# PWR.net
KiCad netlist of a schematic drawn in Altium Designer
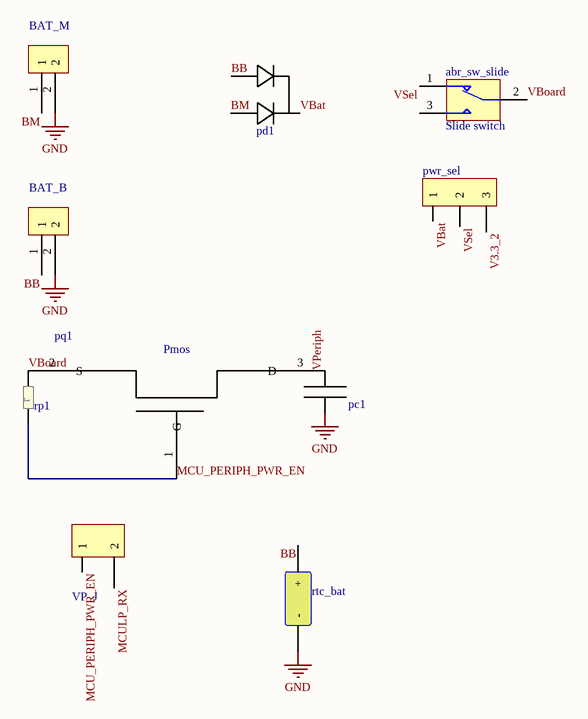
[diagram p0: PWR.SchDoc]

(export (version "E")
  (design (tool "Eeschema 10.0.6"))
  (components
    (comp (ref "abr_sw_slide")
      (value "Slide switch")
      (footprint "abr_sw_slide__r_3d")
      (libsource (lib "lpwireless") (part "Slide switch"))
    )
    (comp (ref "BAT_B")
      (value "YB2 SMD")
      (footprint "abr_sw_yb_2p_3d")
      (libsource (lib "lpwireless") (part "YB2 SMD"))
    )
    (comp (ref "BAT_M")
      (value "YB2 SMD")
      (footprint "abr_sw_yb_2p_3d")
      (libsource (lib "lpwireless") (part "YB2 SMD"))
    )
    (comp (ref "pc1")
      (value "100nf")
      (footprint "abr_cap_0805_3d")
      (libsource (lib "abr_smd_0805_all") (part "abr_cap_0805"))
    )
    (comp (ref "pd1")
      (value "abr_diode_shotkey")
      (footprint "abr_diode_bat54c_3d")
      (libsource (lib "abr_diode_smd") (part "abr_diode_shatkey_bat54c"))
    )
    (comp (ref "pq1")
      (value "irlm6402")
      (footprint "irlm6402")
      (libsource (lib "abr_transistor_smd") (part "irlm6402"))
    )
    (comp (ref "pwr_sel")
      (value "pin header 2mm")
      (footprint "abr_ph_3x1_2mm_3d_male")
      (libsource (lib "abr_ph_2mm_96_02") (part "abr_ph_3x1_2mm"))
    )
    (comp (ref "rp1")
      (value "100k")
      (footprint "abr_res_0805_3d")
      (libsource (lib "abr_smd_0805_all") (part "abr_res_0805"))
    )
    (comp (ref "rtc_bat")
      (value "battery holder")
      (footprint "abr_bh_cr2332_3d")
      (libsource (lib "abr_battery_related_96_02") (part "abr_bh_rtc"))
    )
    (comp (ref "VP_J")
      (value "pin header 2mm")
      (footprint "abr_ph_2x1_2mm_3d_male")
      (libsource (lib "abr_ph_2mm_96_02") (part "abr_2x1_2mm"))
    )
  )
  (nets
    (net (code "1") (name "/BB") (class "Default")
      (node (ref "BAT_B") (pin "1") (pinfunction "1_1") (pintype "passive"))
      (node (ref "pd1") (pin "1") (pinfunction "4_1") (pintype "passive"))
      (node (ref "rtc_bat") (pin "1") (pinfunction "+_1") (pintype "passive"))
    )
    (net (code "2") (name "/BM") (class "Default")
      (node (ref "BAT_M") (pin "1") (pinfunction "1_1") (pintype "passive"))
      (node (ref "pd1") (pin "2") (pinfunction "2_2") (pintype "passive"))
    )
    (net (code "3") (name "/MCULP_RX") (class "Default")
      (node (ref "VP_J") (pin "2") (pinfunction "2_2") (pintype "passive"))
    )
    (net (code "4") (name "/MCU_PERIPH_PWR_EN") (class "Default")
      (node (ref "VP_J") (pin "1") (pinfunction "1_1") (pintype "passive"))
      (node (ref "pq1") (pin "1") (pinfunction "G_1") (pintype "passive"))
      (node (ref "rp1") (pin "0") (pinfunction "0_0") (pintype "passive"))
    )
    (net (code "5") (name "/V3.3_2") (class "Default")
      (node (ref "pwr_sel") (pin "3") (pinfunction "3_3") (pintype "passive"))
    )
    (net (code "6") (name "/VBat") (class "Default")
      (node (ref "pd1") (pin "3") (pinfunction "5_3") (pintype "passive"))
      (node (ref "pwr_sel") (pin "1") (pinfunction "1_1") (pintype "passive"))
    )
    (net (code "7") (name "/VBoard") (class "Default")
      (node (ref "abr_sw_slide") (pin "2") (pinfunction "2_2") (pintype "passive"))
      (node (ref "pq1") (pin "2") (pinfunction "S_2") (pintype "passive"))
      (node (ref "rp1") (pin "1") (pinfunction "0_1") (pintype "passive"))
    )
    (net (code "8") (name "/VPeriph") (class "Default")
      (node (ref "pc1") (pin "0") (pinfunction "2_0") (pintype "passive"))
      (node (ref "pq1") (pin "3") (pinfunction "D_3") (pintype "passive"))
    )
    (net (code "9") (name "/VSel") (class "Default")
      (node (ref "abr_sw_slide") (pin "1") (pinfunction "1_1") (pintype "passive"))
      (node (ref "pwr_sel") (pin "2") (pinfunction "2_2") (pintype "passive"))
    )
    (net (code "10") (name "GND") (class "Default")
      (node (ref "BAT_B") (pin "2") (pinfunction "2_2") (pintype "passive"))
      (node (ref "BAT_M") (pin "2") (pinfunction "2_2") (pintype "passive"))
      (node (ref "pc1") (pin "1") (pinfunction "10_1") (pintype "passive"))
      (node (ref "rtc_bat") (pin "2") (pinfunction "-_2") (pintype "passive"))
    )
    (net (code "11") (name "unconnected-(abr_sw_slide-Pad3)") (class "Default")
      (node (ref "abr_sw_slide") (pin "3") (pinfunction "3_3") (pintype "passive"))
    )
  )
)
